# porta_OU_M.net
KiCad netlist of a schematic drawn in EAGLE
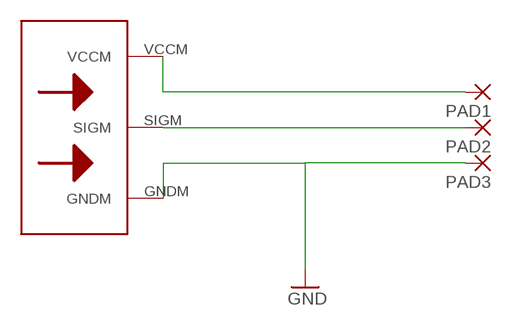
[diagram p0: schematic, sheet 1]

(export (version "E")
  (design (tool "Eeschema 10.0.6"))
  (components
    (comp (ref "PAD1")
      (value "SMD5")
      (footprint "eagle-import:SMD2,54-5,08")
      (libsource (lib "eagle-import") (part "SMD5"))
    )
    (comp (ref "PAD2")
      (value "SMD5")
      (footprint "eagle-import:SMD2,54-5,08")
      (libsource (lib "eagle-import") (part "SMD5"))
    )
    (comp (ref "PAD3")
      (value "SMD5")
      (footprint "eagle-import:SMD2,54-5,08")
      (libsource (lib "eagle-import") (part "SMD5"))
    )
    (comp (ref "U$1")
      (value "BITWIREM")
      (footprint "eagle-import:BITWIREM")
      (libsource (lib "eagle-import") (part "BITWIREM"))
    )
  )
  (nets
    (net (code "1") (name "GND") (class "Default")
      (node (ref "PAD3") (pin "1") (pinfunction "P_1") (pintype "passive"))
      (node (ref "U$1") (pin "GNDM") (pinfunction "GNDM_GNDM") (pintype "bidirectional"))
    )
    (net (code "2") (name "Net-(PAD1-P)") (class "Default")
      (node (ref "PAD1") (pin "1") (pinfunction "P_1") (pintype "passive"))
      (node (ref "U$1") (pin "VCCM") (pinfunction "VCCM_VCCM") (pintype "bidirectional"))
    )
    (net (code "3") (name "Net-(PAD2-P)") (class "Default")
      (node (ref "PAD2") (pin "1") (pinfunction "P_1") (pintype "passive"))
      (node (ref "U$1") (pin "SIGM") (pinfunction "SIGM_SIGM") (pintype "bidirectional"))
    )
  )
)
